# 04-AD9546-Main.net
KiCad netlist of a schematic drawn in Altium Designer
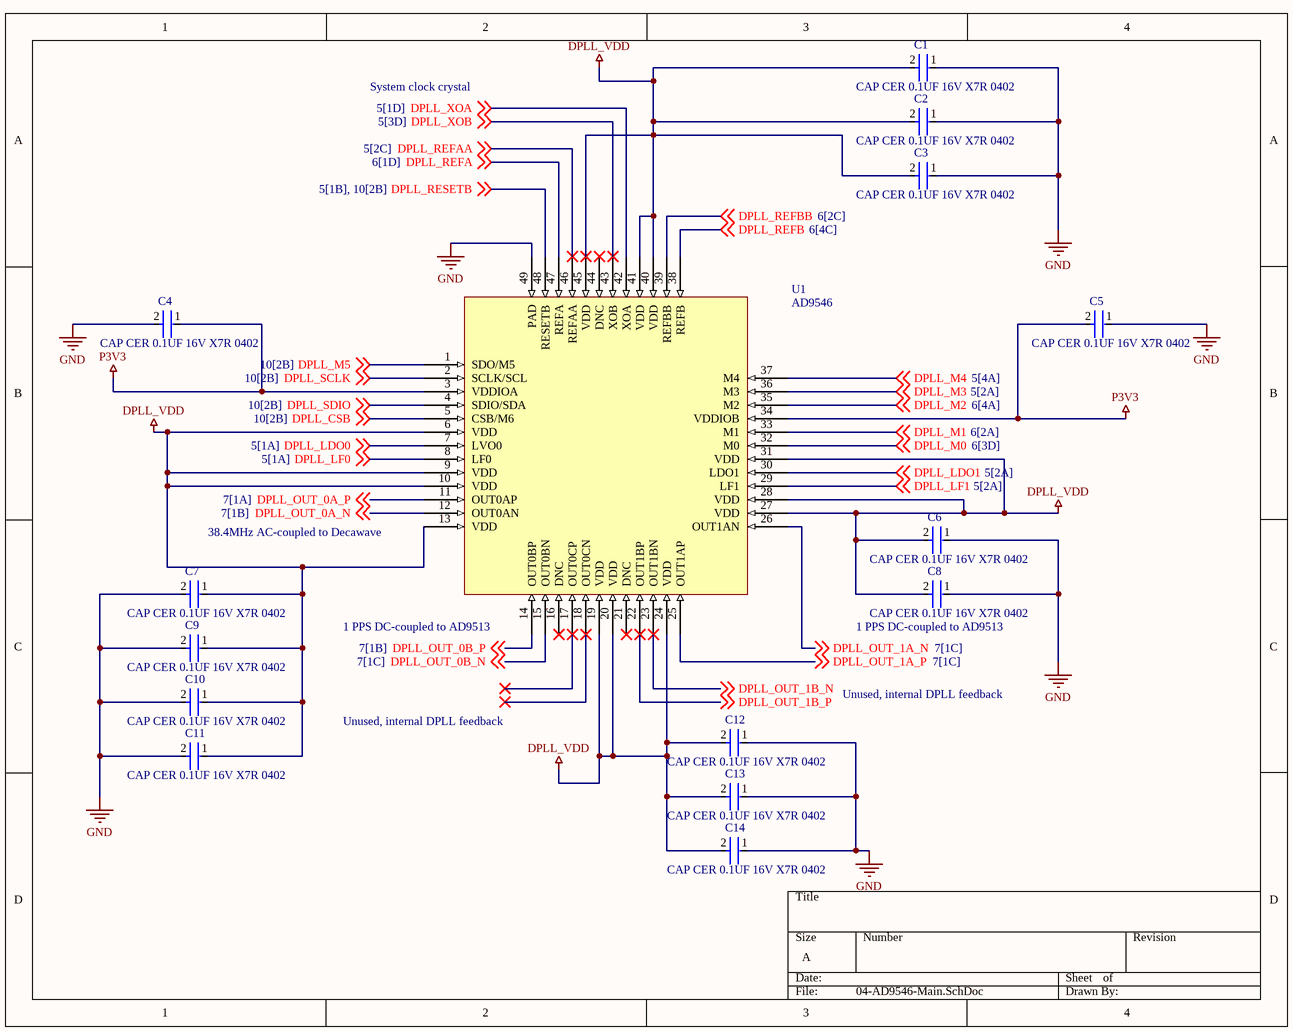
[diagram p0: 04-AD9546-Main.SchDoc]

(export (version "E")
  (design (tool "Eeschema 10.0.6"))
  (components
    (comp (ref "C1")
      (value "GRM155R71C104KA88D")
      (footprint "FP-GRM15-MFG")
      (description "CAP CER 0.1UF 16V X7R 0402")
      (fields
        (field (name "TOLERANCE") "10%")
        (field (name "OCTOPART") "https://octopart.com/grm155r71c104ka88d-murata-196880")
        (field (name "DIGIKEY DESCRIPTION") "CAP CER 0.1UF 16V X7R 0402")
      )
      (libsource (lib "Altium Content Vault") (part "236180d848d6139a670b325ea6854c9"))
    )
    (comp (ref "C2")
      (value "GRM155R71C104KA88D")
      (footprint "FP-GRM15-MFG")
      (description "CAP CER 0.1UF 16V X7R 0402")
      (fields
        (field (name "TOLERANCE") "10%")
        (field (name "OCTOPART") "https://octopart.com/grm155r71c104ka88d-murata-196880")
        (field (name "DIGIKEY DESCRIPTION") "CAP CER 0.1UF 16V X7R 0402")
      )
      (libsource (lib "Altium Content Vault") (part "236180d848d6139a670b325ea6854c9"))
    )
    (comp (ref "C3")
      (value "GRM155R71C104KA88D")
      (footprint "FP-GRM15-MFG")
      (description "CAP CER 0.1UF 16V X7R 0402")
      (fields
        (field (name "TOLERANCE") "10%")
        (field (name "OCTOPART") "https://octopart.com/grm155r71c104ka88d-murata-196880")
        (field (name "DIGIKEY DESCRIPTION") "CAP CER 0.1UF 16V X7R 0402")
      )
      (libsource (lib "Altium Content Vault") (part "236180d848d6139a670b325ea6854c9"))
    )
    (comp (ref "C4")
      (value "GRM155R71C104KA88D")
      (footprint "FP-GRM15-MFG")
      (description "CAP CER 0.1UF 16V X7R 0402")
      (fields
        (field (name "TOLERANCE") "10%")
        (field (name "OCTOPART") "https://octopart.com/grm155r71c104ka88d-murata-196880")
        (field (name "DIGIKEY DESCRIPTION") "CAP CER 0.1UF 16V X7R 0402")
      )
      (libsource (lib "Altium Content Vault") (part "236180d848d6139a670b325ea6854c9"))
    )
    (comp (ref "C5")
      (value "GRM155R71C104KA88D")
      (footprint "FP-GRM15-MFG")
      (description "CAP CER 0.1UF 16V X7R 0402")
      (fields
        (field (name "TOLERANCE") "10%")
        (field (name "OCTOPART") "https://octopart.com/grm155r71c104ka88d-murata-196880")
        (field (name "DIGIKEY DESCRIPTION") "CAP CER 0.1UF 16V X7R 0402")
      )
      (libsource (lib "Altium Content Vault") (part "236180d848d6139a670b325ea6854c9"))
    )
    (comp (ref "C6")
      (value "GRM155R71C104KA88D")
      (footprint "FP-GRM15-MFG")
      (description "CAP CER 0.1UF 16V X7R 0402")
      (fields
        (field (name "TOLERANCE") "10%")
        (field (name "OCTOPART") "https://octopart.com/grm155r71c104ka88d-murata-196880")
        (field (name "DIGIKEY DESCRIPTION") "CAP CER 0.1UF 16V X7R 0402")
      )
      (libsource (lib "Altium Content Vault") (part "236180d848d6139a670b325ea6854c9"))
    )
    (comp (ref "C7")
      (value "GRM155R71C104KA88D")
      (footprint "FP-GRM15-MFG")
      (description "CAP CER 0.1UF 16V X7R 0402")
      (fields
        (field (name "TOLERANCE") "10%")
        (field (name "OCTOPART") "https://octopart.com/grm155r71c104ka88d-murata-196880")
        (field (name "DIGIKEY DESCRIPTION") "CAP CER 0.1UF 16V X7R 0402")
      )
      (libsource (lib "Altium Content Vault") (part "236180d848d6139a670b325ea6854c9"))
    )
    (comp (ref "C8")
      (value "GRM155R71C104KA88D")
      (footprint "FP-GRM15-MFG")
      (description "CAP CER 0.1UF 16V X7R 0402")
      (fields
        (field (name "TOLERANCE") "10%")
        (field (name "OCTOPART") "https://octopart.com/grm155r71c104ka88d-murata-196880")
        (field (name "DIGIKEY DESCRIPTION") "CAP CER 0.1UF 16V X7R 0402")
      )
      (libsource (lib "Altium Content Vault") (part "236180d848d6139a670b325ea6854c9"))
    )
    (comp (ref "C9")
      (value "GRM155R71C104KA88D")
      (footprint "FP-GRM15-MFG")
      (description "CAP CER 0.1UF 16V X7R 0402")
      (fields
        (field (name "TOLERANCE") "10%")
        (field (name "OCTOPART") "https://octopart.com/grm155r71c104ka88d-murata-196880")
        (field (name "DIGIKEY DESCRIPTION") "CAP CER 0.1UF 16V X7R 0402")
      )
      (libsource (lib "Altium Content Vault") (part "236180d848d6139a670b325ea6854c9"))
    )
    (comp (ref "C10")
      (value "GRM155R71C104KA88D")
      (footprint "FP-GRM15-MFG")
      (description "CAP CER 0.1UF 16V X7R 0402")
      (fields
        (field (name "TOLERANCE") "10%")
        (field (name "OCTOPART") "https://octopart.com/grm155r71c104ka88d-murata-196880")
        (field (name "DIGIKEY DESCRIPTION") "CAP CER 0.1UF 16V X7R 0402")
      )
      (libsource (lib "Altium Content Vault") (part "236180d848d6139a670b325ea6854c9"))
    )
    (comp (ref "C11")
      (value "GRM155R71C104KA88D")
      (footprint "FP-GRM15-MFG")
      (description "CAP CER 0.1UF 16V X7R 0402")
      (fields
        (field (name "TOLERANCE") "10%")
        (field (name "OCTOPART") "https://octopart.com/grm155r71c104ka88d-murata-196880")
        (field (name "DIGIKEY DESCRIPTION") "CAP CER 0.1UF 16V X7R 0402")
      )
      (libsource (lib "Altium Content Vault") (part "236180d848d6139a670b325ea6854c9"))
    )
    (comp (ref "C12")
      (value "GRM155R71C104KA88D")
      (footprint "FP-GRM15-MFG")
      (description "CAP CER 0.1UF 16V X7R 0402")
      (fields
        (field (name "TOLERANCE") "10%")
        (field (name "OCTOPART") "https://octopart.com/grm155r71c104ka88d-murata-196880")
        (field (name "DIGIKEY DESCRIPTION") "CAP CER 0.1UF 16V X7R 0402")
      )
      (libsource (lib "Altium Content Vault") (part "236180d848d6139a670b325ea6854c9"))
    )
    (comp (ref "C13")
      (value "GRM155R71C104KA88D")
      (footprint "FP-GRM15-MFG")
      (description "CAP CER 0.1UF 16V X7R 0402")
      (fields
        (field (name "TOLERANCE") "10%")
        (field (name "OCTOPART") "https://octopart.com/grm155r71c104ka88d-murata-196880")
        (field (name "DIGIKEY DESCRIPTION") "CAP CER 0.1UF 16V X7R 0402")
      )
      (libsource (lib "Altium Content Vault") (part "236180d848d6139a670b325ea6854c9"))
    )
    (comp (ref "C14")
      (value "GRM155R71C104KA88D")
      (footprint "FP-GRM15-MFG")
      (description "CAP CER 0.1UF 16V X7R 0402")
      (fields
        (field (name "TOLERANCE") "10%")
        (field (name "OCTOPART") "https://octopart.com/grm155r71c104ka88d-murata-196880")
        (field (name "DIGIKEY DESCRIPTION") "CAP CER 0.1UF 16V X7R 0402")
      )
      (libsource (lib "Altium Content Vault") (part "236180d848d6139a670b325ea6854c9"))
    )
    (comp (ref "U1") (value "AD9546") (footprint "AD9546") (libsource (lib "TimeStick_Lib") (part "AD9546")))
  )
  (nets
    (net (code "1") (name "DPLL_CSB") (class "Default")
      (node (ref "U1") (pin "5") (pinfunction "CSB/M6_5") (pintype "input"))
    )
    (net (code "2") (name "DPLL_LDO0") (class "Default")
      (node (ref "U1") (pin "7") (pinfunction "LVO0_7") (pintype "input"))
    )
    (net (code "3") (name "DPLL_LDO1") (class "Default")
      (node (ref "U1") (pin "30") (pinfunction "LDO1_30") (pintype "input"))
    )
    (net (code "4") (name "DPLL_LF0") (class "Default")
      (node (ref "U1") (pin "8") (pinfunction "LF0_8") (pintype "input"))
    )
    (net (code "5") (name "DPLL_LF1") (class "Default")
      (node (ref "U1") (pin "29") (pinfunction "LF1_29") (pintype "input"))
    )
    (net (code "6") (name "DPLL_M0") (class "Default")
      (node (ref "U1") (pin "32") (pinfunction "M0_32") (pintype "input"))
    )
    (net (code "7") (name "DPLL_M1") (class "Default")
      (node (ref "U1") (pin "33") (pinfunction "M1_33") (pintype "input"))
    )
    (net (code "8") (name "DPLL_M2") (class "Default")
      (node (ref "U1") (pin "35") (pinfunction "M2_35") (pintype "input"))
    )
    (net (code "9") (name "DPLL_M3") (class "Default")
      (node (ref "U1") (pin "36") (pinfunction "M3_36") (pintype "input"))
    )
    (net (code "10") (name "DPLL_M4") (class "Default")
      (node (ref "U1") (pin "37") (pinfunction "M4_37") (pintype "input"))
    )
    (net (code "11") (name "DPLL_M5") (class "Default")
      (node (ref "U1") (pin "1") (pinfunction "SDO/M5_1") (pintype "input"))
    )
    (net (code "12") (name "DPLL_OUT_0A_N") (class "Default")
      (node (ref "U1") (pin "12") (pinfunction "OUT0AN_12") (pintype "input"))
    )
    (net (code "13") (name "DPLL_OUT_0A_P") (class "Default")
      (node (ref "U1") (pin "11") (pinfunction "OUT0AP_11") (pintype "input"))
    )
    (net (code "14") (name "DPLL_OUT_0B_N") (class "Default")
      (node (ref "U1") (pin "15") (pinfunction "OUT0BN_15") (pintype "input"))
    )
    (net (code "15") (name "DPLL_OUT_0B_P") (class "Default")
      (node (ref "U1") (pin "14") (pinfunction "OUT0BP_14") (pintype "input"))
    )
    (net (code "16") (name "DPLL_OUT_1A_N") (class "Default")
      (node (ref "U1") (pin "26") (pinfunction "OUT1AN_26") (pintype "input"))
    )
    (net (code "17") (name "DPLL_OUT_1A_P") (class "Default")
      (node (ref "U1") (pin "25") (pinfunction "OUT1AP_25") (pintype "input"))
    )
    (net (code "18") (name "DPLL_OUT_1B_N") (class "Default")
      (node (ref "U1") (pin "23") (pinfunction "OUT1BN_23") (pintype "input"))
    )
    (net (code "19") (name "DPLL_OUT_1B_P") (class "Default")
      (node (ref "U1") (pin "22") (pinfunction "OUT1BP_22") (pintype "input"))
    )
    (net (code "20") (name "DPLL_REFA") (class "Default")
      (node (ref "U1") (pin "47") (pinfunction "REFA_47") (pintype "input"))
    )
    (net (code "21") (name "DPLL_REFAA") (class "Default")
      (node (ref "U1") (pin "46") (pinfunction "REFAA_46") (pintype "input"))
    )
    (net (code "22") (name "DPLL_REFB") (class "Default")
      (node (ref "U1") (pin "38") (pinfunction "REFB_38") (pintype "input"))
    )
    (net (code "23") (name "DPLL_REFBB") (class "Default")
      (node (ref "U1") (pin "39") (pinfunction "REFBB_39") (pintype "input"))
    )
    (net (code "24") (name "DPLL_RESETB") (class "Default")
      (node (ref "U1") (pin "48") (pinfunction "RESETB_48") (pintype "input"))
    )
    (net (code "25") (name "DPLL_SCLK") (class "Default")
      (node (ref "U1") (pin "2") (pinfunction "SCLK/SCL_2") (pintype "input"))
    )
    (net (code "26") (name "DPLL_SDIO") (class "Default")
      (node (ref "U1") (pin "4") (pinfunction "SDIO/SDA_4") (pintype "input"))
    )
    (net (code "27") (name "DPLL_VDD") (class "Default")
      (node (ref "C1") (pin "2") (pinfunction "2_2") (pintype "passive"))
      (node (ref "C10") (pin "1") (pinfunction "1_1") (pintype "passive"))
      (node (ref "C11") (pin "1") (pinfunction "1_1") (pintype "passive"))
      (node (ref "C12") (pin "2") (pinfunction "2_2") (pintype "passive"))
      (node (ref "C13") (pin "2") (pinfunction "2_2") (pintype "passive"))
      (node (ref "C14") (pin "2") (pinfunction "2_2") (pintype "passive"))
      (node (ref "C2") (pin "2") (pinfunction "2_2") (pintype "passive"))
      (node (ref "C3") (pin "2") (pinfunction "2_2") (pintype "passive"))
      (node (ref "C6") (pin "2") (pinfunction "2_2") (pintype "passive"))
      (node (ref "C7") (pin "1") (pinfunction "1_1") (pintype "passive"))
      (node (ref "C8") (pin "2") (pinfunction "2_2") (pintype "passive"))
      (node (ref "C9") (pin "1") (pinfunction "1_1") (pintype "passive"))
      (node (ref "U1") (pin "10") (pinfunction "VDD_10") (pintype "input"))
      (node (ref "U1") (pin "13") (pinfunction "VDD_13") (pintype "input"))
      (node (ref "U1") (pin "19") (pinfunction "VDD_19") (pintype "input"))
      (node (ref "U1") (pin "20") (pinfunction "VDD_20") (pintype "input"))
      (node (ref "U1") (pin "24") (pinfunction "VDD_24") (pintype "input"))
      (node (ref "U1") (pin "27") (pinfunction "VDD_27") (pintype "input"))
      (node (ref "U1") (pin "28") (pinfunction "VDD_28") (pintype "input"))
      (node (ref "U1") (pin "31") (pinfunction "VDD_31") (pintype "input"))
      (node (ref "U1") (pin "40") (pinfunction "VDD_40") (pintype "input"))
      (node (ref "U1") (pin "41") (pinfunction "VDD_41") (pintype "input"))
      (node (ref "U1") (pin "45") (pinfunction "VDD_45") (pintype "input"))
      (node (ref "U1") (pin "6") (pinfunction "VDD_6") (pintype "input"))
      (node (ref "U1") (pin "9") (pinfunction "VDD_9") (pintype "input"))
    )
    (net (code "28") (name "DPLL_XOA") (class "Default")
      (node (ref "U1") (pin "42") (pinfunction "XOA_42") (pintype "input"))
    )
    (net (code "29") (name "DPLL_XOB") (class "Default")
      (node (ref "U1") (pin "43") (pinfunction "XOB_43") (pintype "input"))
    )
    (net (code "30") (name "GND") (class "Default")
      (node (ref "C1") (pin "1") (pinfunction "1_1") (pintype "passive"))
      (node (ref "C10") (pin "2") (pinfunction "2_2") (pintype "passive"))
      (node (ref "C11") (pin "2") (pinfunction "2_2") (pintype "passive"))
      (node (ref "C12") (pin "1") (pinfunction "1_1") (pintype "passive"))
      (node (ref "C13") (pin "1") (pinfunction "1_1") (pintype "passive"))
      (node (ref "C14") (pin "1") (pinfunction "1_1") (pintype "passive"))
      (node (ref "C2") (pin "1") (pinfunction "1_1") (pintype "passive"))
      (node (ref "C3") (pin "1") (pinfunction "1_1") (pintype "passive"))
      (node (ref "C4") (pin "2") (pinfunction "2_2") (pintype "passive"))
      (node (ref "C5") (pin "1") (pinfunction "1_1") (pintype "passive"))
      (node (ref "C6") (pin "1") (pinfunction "1_1") (pintype "passive"))
      (node (ref "C7") (pin "2") (pinfunction "2_2") (pintype "passive"))
      (node (ref "C8") (pin "1") (pinfunction "1_1") (pintype "passive"))
      (node (ref "C9") (pin "2") (pinfunction "2_2") (pintype "passive"))
      (node (ref "U1") (pin "49") (pinfunction "PAD_49") (pintype "input"))
    )
    (net (code "31") (name "P3V3") (class "Default")
      (node (ref "C4") (pin "1") (pinfunction "1_1") (pintype "passive"))
      (node (ref "C5") (pin "2") (pinfunction "2_2") (pintype "passive"))
      (node (ref "U1") (pin "3") (pinfunction "VDDIOA_3") (pintype "input"))
      (node (ref "U1") (pin "34") (pinfunction "VDDIOB_34") (pintype "input"))
    )
    (net (code "32") (name "unconnected-(U1-DNC-Pad16)") (class "Default")
      (node (ref "U1") (pin "16") (pinfunction "DNC_16") (pintype "input+no_connect"))
    )
    (net (code "33") (name "unconnected-(U1-DNC-Pad21)") (class "Default")
      (node (ref "U1") (pin "21") (pinfunction "DNC_21") (pintype "input+no_connect"))
    )
    (net (code "34") (name "unconnected-(U1-DNC-Pad44)") (class "Default")
      (node (ref "U1") (pin "44") (pinfunction "DNC_44") (pintype "input+no_connect"))
    )
    (net (code "35") (name "unconnected-(U1-OUT0CN-Pad18)") (class "Default")
      (node (ref "U1") (pin "18") (pinfunction "OUT0CN_18") (pintype "input+no_connect"))
    )
    (net (code "36") (name "unconnected-(U1-OUT0CP-Pad17)") (class "Default")
      (node (ref "U1") (pin "17") (pinfunction "OUT0CP_17") (pintype "input+no_connect"))
    )
  )
)
